# BlinkBoard.net
KiCad netlist of a schematic drawn in Altium Designer
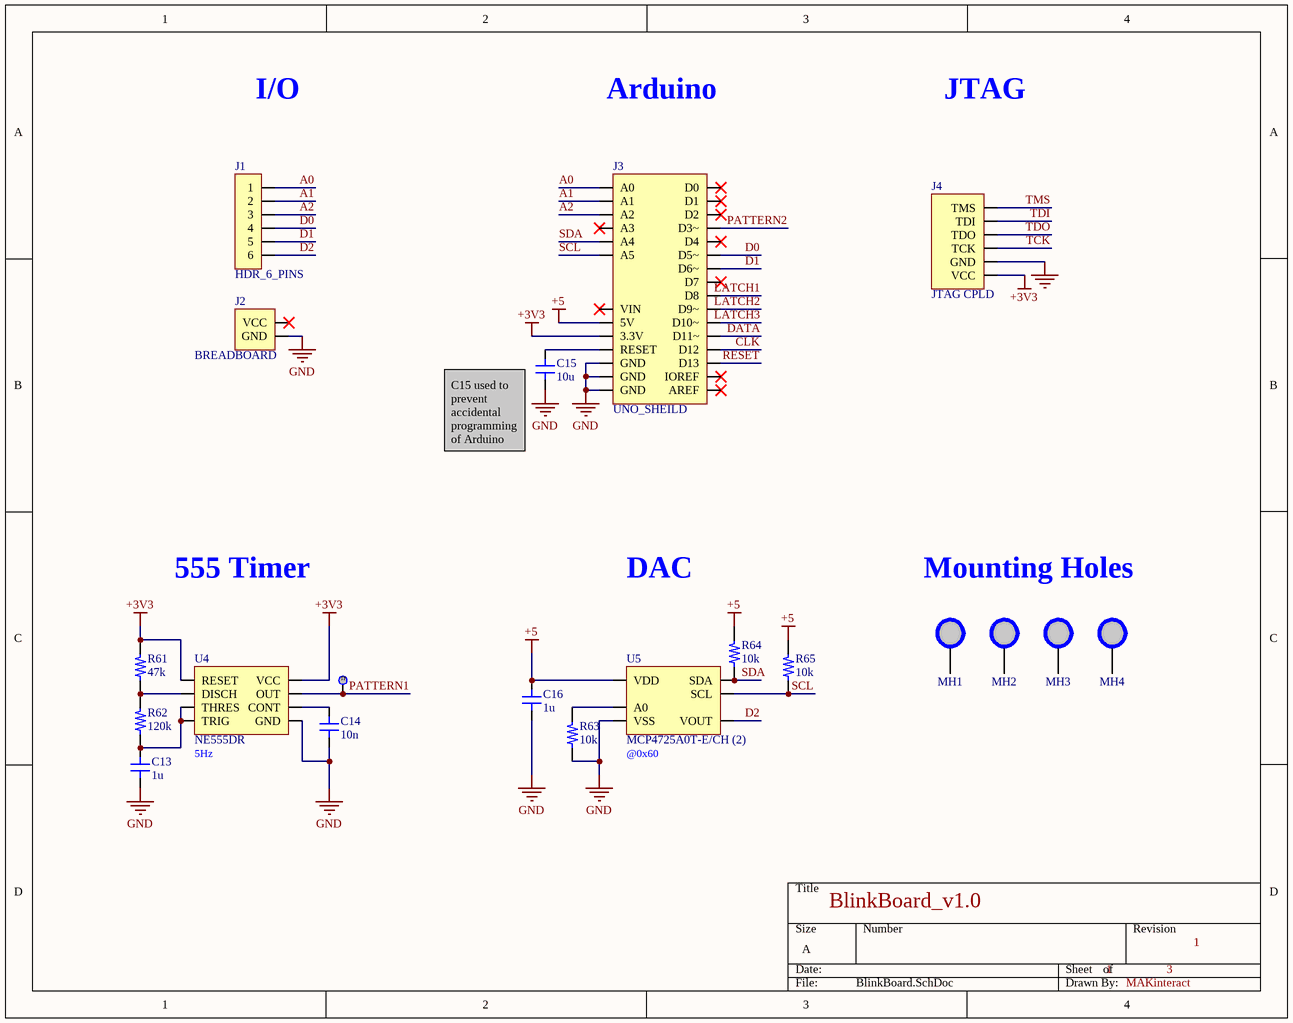
[diagram p0: BlinkBoard.SchDoc]

(export (version "E")
  (design (tool "Eeschema 10.0.6"))
  (components
    (comp (ref "C13")
      (value "1u")
      (footprint "C0805")
      (fields
        (field (name "MANUFACTURER") "Yageo")
        (field (name "MANUFACTURER PART NUMBER") "CC0805ZRY5V8BB105")
        (field (name "TOLERANCE") "80%")
      )
      (libsource (lib "LightBoard_v1.0") (part "C0805_1u"))
    )
    (comp (ref "C14")
      (value "10n")
      (footprint "C0402")
      (description "Cap Ceramic 0.01uF 10V X7R 10% SMD 0402 125C Paper T/R")
      (fields
        (field (name "MANUFACTURER") "Yageo")
        (field (name "MANUFACTURER PART NUMBER") "CC0402KRX7R6BB103")
      )
      (libsource (lib "LightBoard_v1.0") (part "C0402_10n"))
    )
    (comp (ref "C15")
      (value "10u")
      (footprint "C0805")
      (description "Cap Ceramic 10uF 6.3V X5R 10% SMD 0805 85C Paper T/R")
      (fields
        (field (name "MANUFACTURER") "Yageo")
        (field (name "MANUFACTURER PART NUMBER") "CC0805KRX5R5BB106")
      )
      (libsource (lib "BlinkBoard") (part "C0804_10u"))
    )
    (comp (ref "C16")
      (value "1u")
      (footprint "C0805")
      (fields
        (field (name "MANUFACTURER") "Yageo")
        (field (name "MANUFACTURER PART NUMBER") "CC0805ZRY5V8BB105")
        (field (name "TOLERANCE") "80%")
      )
      (libsource (lib "LightBoard_v1.0") (part "C0805_1u"))
    )
    (comp (ref "J1")
      (value "HDR_6_PINS")
      (footprint "HDR6_100mil")
      (description "Sockets to connect to Arduino pins")
      (libsource (lib "LightBoard_v1.0") (part "H_ARDUPINS"))
    )
    (comp (ref "J2")
      (value "BREADBOARD")
      (footprint "BREADBOARD")
      (description "26*2 ROWS")
      (libsource (lib "LightBoard_v1.0") (part "BREADBOARD"))
    )
    (comp (ref "J3")
      (value "UNO_SHEILD")
      (footprint "ARDUINO_UNO_SHIELD")
      (description "Arduino UNO shield")
      (fields (field (name "MANUFACTURER") "Arduino") (field (name "MANUFACTURER PART NUMBER") "A000073"))
      (libsource (lib "LightBoard_v1.0") (part "ARDUINO_UNO_SHIELD"))
    )
    (comp (ref "J4")
      (value "JTAG CPLD")
      (footprint "JTAG")
      (description "Socket to connect to JTAG")
      (libsource (lib "LightBoard_v1.0") (part "H_JTAG"))
    )
    (comp (ref "MH1")
      (value "MH 3.2mm NP")
      (footprint "MH3.2MM")
      (description "Mounting hole 3.2mm non plated")
      (libsource (lib "LightBoard_v1.0") (part "MHNP"))
    )
    (comp (ref "MH2")
      (value "MH 3.2mm NP")
      (footprint "MH3.2MM")
      (description "Mounting hole 3.2mm non plated")
      (libsource (lib "LightBoard_v1.0") (part "MHNP"))
    )
    (comp (ref "MH3")
      (value "MH 3.2mm NP")
      (footprint "MH3.2MM")
      (description "Mounting hole 3.2mm non plated")
      (libsource (lib "LightBoard_v1.0") (part "MHNP"))
    )
    (comp (ref "MH4")
      (value "MH 3.2mm NP")
      (footprint "MH3.2MM")
      (description "Mounting hole 3.2mm non plated")
      (libsource (lib "LightBoard_v1.0") (part "MHNP"))
    )
    (comp (ref "R61")
      (value "47k")
      (footprint "RES0402")
      (fields
        (field (name "MANUFACTURER") "Yageo")
        (field (name "MANUFACTURER PART NUMBER") "RC0402JR-0747KL")
        (field (name "TOLERANCE") "5%")
      )
      (libsource (lib "LightBoard_v1.0") (part "R0402_47K"))
    )
    (comp (ref "R62")
      (value "120k")
      (footprint "RES0402")
      (description "RES SMD 120K OHM 5% 1/16W 0402")
      (fields
        (field (name "MANUFACTURER") "Yageo")
        (field (name "MANUFACTURER PART NUMBER") "RC0402JR-07120KL")
      )
      (libsource (lib "LightBoard_v1.0") (part "R0402_120K"))
    )
    (comp (ref "R63")
      (value "10k")
      (footprint "RES0402")
      (description "RES SMD 10K OHM 1% 1/16W 0402")
      (fields
        (field (name "MANUFACTURER") "Yageo")
        (field (name "MANUFACTURER PART NUMBER") "RC0402FR-0710KP")
      )
      (libsource (lib "LightBoard_v1.0") (part "R0402_10K"))
    )
    (comp (ref "R64")
      (value "10k")
      (footprint "RES0402")
      (description "RES SMD 10K OHM 1% 1/16W 0402")
      (fields
        (field (name "MANUFACTURER") "Yageo")
        (field (name "MANUFACTURER PART NUMBER") "RC0402FR-0710KP")
      )
      (libsource (lib "LightBoard_v1.0") (part "R0402_10K"))
    )
    (comp (ref "R65")
      (value "10k")
      (footprint "RES0402")
      (description "RES SMD 10K OHM 1% 1/16W 0402")
      (fields
        (field (name "MANUFACTURER") "Yageo")
        (field (name "MANUFACTURER PART NUMBER") "RC0402FR-0710KP")
      )
      (libsource (lib "LightBoard_v1.0") (part "R0402_10K"))
    )
    (comp (ref "TP1")
      (value "TEST POINT")
      (footprint "TEST POINT")
      (libsource (lib "LightBoard_v1.0") (part "TEST POINT"))
    )
    (comp (ref "U4")
      (value "NE555DR")
      (footprint "8-SOIC")
      (description "TEXAS INSTRUMENTS         NE555DR.             TIMER, SINGLE, 500KHZ, 16V, SOIC-8")
      (fields (field (name "MANUFACTURER") "Texas Instruments"))
      (libsource (lib "LightBoard_v1.0") (part "555"))
    )
    (comp (ref "U5")
      (value "MCP4725A0T-E/CH (2)")
      (footprint "SOT23-6")
      (description "DAC 1-CH Resistor-String 12-bit 6-Pin SOT-23A T/R")
      (fields
        (field (name "MANUFACTURER") "Microchip")
        (field (name "MANUFACTURER PART NUMBER") "MCP4725A0T-E/CH")
      )
      (libsource (lib "LightBoard_v1.0") (part "MCP4725A0T"))
    )
  )
  (nets
    (net (code "1") (name "+3V3") (class "Default")
      (node (ref "J3") (pin "27") (pinfunction "3.3V_27") (pintype "passive"))
      (node (ref "J4") (pin "6") (pinfunction "VCC_6") (pintype "passive"))
      (node (ref "R61") (pin "2") (pinfunction "2_2") (pintype "passive"))
      (node (ref "U4") (pin "4") (pinfunction "RESET_4") (pintype "passive"))
      (node (ref "U4") (pin "8") (pinfunction "VCC_8") (pintype "passive"))
    )
    (net (code "2") (name "+5") (class "Default")
      (node (ref "C16") (pin "2") (pinfunction "2_2") (pintype "passive"))
      (node (ref "J3") (pin "26") (pinfunction "5V_26") (pintype "passive"))
      (node (ref "R64") (pin "2") (pinfunction "2_2") (pintype "passive"))
      (node (ref "R65") (pin "2") (pinfunction "2_2") (pintype "passive"))
      (node (ref "U5") (pin "3") (pinfunction "VDD_3") (pintype "passive"))
    )
    (net (code "3") (name "/A0") (class "Default")
      (node (ref "J1") (pin "1") (pinfunction "1_1") (pintype "passive"))
      (node (ref "J3") (pin "22") (pinfunction "A0_22") (pintype "passive"))
    )
    (net (code "4") (name "/A1") (class "Default")
      (node (ref "J1") (pin "2") (pinfunction "2_2") (pintype "passive"))
      (node (ref "J3") (pin "21") (pinfunction "A1_21") (pintype "passive"))
    )
    (net (code "5") (name "/A2") (class "Default")
      (node (ref "J1") (pin "3") (pinfunction "3_3") (pintype "passive"))
      (node (ref "J3") (pin "20") (pinfunction "A2_20") (pintype "passive"))
    )
    (net (code "6") (name "/CLK") (class "Default")
      (node (ref "J3") (pin "13") (pinfunction "D12_13") (pintype "passive"))
    )
    (net (code "7") (name "/D0") (class "Default")
      (node (ref "J1") (pin "4") (pinfunction "4_4") (pintype "passive"))
      (node (ref "J3") (pin "6") (pinfunction "D5~_6") (pintype "passive"))
    )
    (net (code "8") (name "/D1") (class "Default")
      (node (ref "J1") (pin "5") (pinfunction "5_5") (pintype "passive"))
      (node (ref "J3") (pin "7") (pinfunction "D6~_7") (pintype "passive"))
    )
    (net (code "9") (name "/D2") (class "Default")
      (node (ref "J1") (pin "6") (pinfunction "6_6") (pintype "passive"))
      (node (ref "U5") (pin "1") (pinfunction "VOUT_1") (pintype "passive"))
    )
    (net (code "10") (name "/DATA") (class "Default")
      (node (ref "J3") (pin "12") (pinfunction "D11~_12") (pintype "passive"))
    )
    (net (code "11") (name "/LATCH1") (class "Default")
      (node (ref "J3") (pin "9") (pinfunction "D8_9") (pintype "passive"))
    )
    (net (code "12") (name "/LATCH2") (class "Default")
      (node (ref "J3") (pin "10") (pinfunction "D9~_10") (pintype "passive"))
    )
    (net (code "13") (name "/LATCH3") (class "Default")
      (node (ref "J3") (pin "11") (pinfunction "D10~_11") (pintype "passive"))
    )
    (net (code "14") (name "/PATTERN1") (class "Default")
      (node (ref "TP1") (pin "1") (pinfunction "1_1") (pintype "passive"))
      (node (ref "U4") (pin "3") (pinfunction "OUT_3") (pintype "passive"))
    )
    (net (code "15") (name "/PATTERN2") (class "Default")
      (node (ref "J3") (pin "4") (pinfunction "D3~_4") (pintype "passive"))
    )
    (net (code "16") (name "/RESET") (class "Default")
      (node (ref "J3") (pin "14") (pinfunction "D13_14") (pintype "passive"))
    )
    (net (code "17") (name "/SCL") (class "Default")
      (node (ref "J3") (pin "17") (pinfunction "A5_17") (pintype "passive"))
      (node (ref "R65") (pin "1") (pinfunction "1_1") (pintype "passive"))
      (node (ref "U5") (pin "5") (pinfunction "SCL_5") (pintype "passive"))
    )
    (net (code "18") (name "/SDA") (class "Default")
      (node (ref "J3") (pin "18") (pinfunction "A4_18") (pintype "passive"))
      (node (ref "R64") (pin "1") (pinfunction "1_1") (pintype "passive"))
      (node (ref "U5") (pin "4") (pinfunction "SDA_4") (pintype "passive"))
    )
    (net (code "19") (name "/TCK") (class "Default")
      (node (ref "J4") (pin "4") (pinfunction "TCK_4") (pintype "passive"))
    )
    (net (code "20") (name "/TDI") (class "Default")
      (node (ref "J4") (pin "2") (pinfunction "TDI_2") (pintype "passive"))
    )
    (net (code "21") (name "/TDO") (class "Default")
      (node (ref "J4") (pin "3") (pinfunction "TDO_3") (pintype "passive"))
    )
    (net (code "22") (name "/TMS") (class "Default")
      (node (ref "J4") (pin "1") (pinfunction "TMS_1") (pintype "passive"))
    )
    (net (code "23") (name "GND") (class "Default")
      (node (ref "C13") (pin "1") (pinfunction "1_1") (pintype "passive"))
      (node (ref "C14") (pin "1") (pinfunction "1_1") (pintype "passive"))
      (node (ref "C15") (pin "1") (pinfunction "1_1") (pintype "passive"))
      (node (ref "C16") (pin "1") (pinfunction "1_1") (pintype "passive"))
      (node (ref "J2") (pin "2") (pinfunction "GND_2") (pintype "passive"))
      (node (ref "J3") (pin "15") (pinfunction "GND_15") (pintype "passive"))
      (node (ref "J3") (pin "24") (pinfunction "GND_24") (pintype "passive"))
      (node (ref "J3") (pin "25") (pinfunction "GND_25") (pintype "passive"))
      (node (ref "J4") (pin "5") (pinfunction "GND_5") (pintype "passive"))
      (node (ref "R63") (pin "1") (pinfunction "1_1") (pintype "passive"))
      (node (ref "U4") (pin "1") (pinfunction "GND_1") (pintype "passive"))
      (node (ref "U5") (pin "2") (pinfunction "VSS_2") (pintype "passive"))
    )
    (net (code "24") (name "Net-(J3-RESET)") (class "Default")
      (node (ref "C15") (pin "2") (pinfunction "2_2") (pintype "passive"))
      (node (ref "J3") (pin "28") (pinfunction "RESET_28") (pintype "passive"))
    )
    (net (code "25") (name "Net-(U4-CONT)") (class "Default")
      (node (ref "C14") (pin "2") (pinfunction "2_2") (pintype "passive"))
      (node (ref "U4") (pin "5") (pinfunction "CONT_5") (pintype "passive"))
    )
    (net (code "26") (name "Net-(U4-DISCH)") (class "Default")
      (node (ref "R61") (pin "1") (pinfunction "1_1") (pintype "passive"))
      (node (ref "R62") (pin "2") (pinfunction "2_2") (pintype "passive"))
      (node (ref "U4") (pin "7") (pinfunction "DISCH_7") (pintype "passive"))
    )
    (net (code "27") (name "Net-(U4-THRES)") (class "Default")
      (node (ref "C13") (pin "2") (pinfunction "2_2") (pintype "passive"))
      (node (ref "R62") (pin "1") (pinfunction "1_1") (pintype "passive"))
      (node (ref "U4") (pin "2") (pinfunction "TRIG_2") (pintype "passive"))
      (node (ref "U4") (pin "6") (pinfunction "THRES_6") (pintype "passive"))
    )
    (net (code "28") (name "Net-(U5-A0)") (class "Default")
      (node (ref "R63") (pin "2") (pinfunction "2_2") (pintype "passive"))
      (node (ref "U5") (pin "6") (pinfunction "A0_6") (pintype "passive"))
    )
    (net (code "29") (name "unconnected-(J2-VCC-Pad1)") (class "Default")
      (node (ref "J2") (pin "1") (pinfunction "VCC_1") (pintype "passive+no_connect"))
    )
    (net (code "30") (name "unconnected-(J3-A3-Pad19)") (class "Default")
      (node (ref "J3") (pin "19") (pinfunction "A3_19") (pintype "passive+no_connect"))
    )
    (net (code "31") (name "unconnected-(J3-AREF-Pad16)") (class "Default")
      (node (ref "J3") (pin "16") (pinfunction "AREF_16") (pintype "passive+no_connect"))
    )
    (net (code "32") (name "unconnected-(J3-D0-Pad1)") (class "Default")
      (node (ref "J3") (pin "1") (pinfunction "D0_1") (pintype "passive+no_connect"))
    )
    (net (code "33") (name "unconnected-(J3-D1-Pad2)") (class "Default")
      (node (ref "J3") (pin "2") (pinfunction "D1_2") (pintype "passive+no_connect"))
    )
    (net (code "34") (name "unconnected-(J3-D2-Pad3)") (class "Default")
      (node (ref "J3") (pin "3") (pinfunction "D2_3") (pintype "passive+no_connect"))
    )
    (net (code "35") (name "unconnected-(J3-D4-Pad5)") (class "Default")
      (node (ref "J3") (pin "5") (pinfunction "D4_5") (pintype "passive+no_connect"))
    )
    (net (code "36") (name "unconnected-(J3-D7-Pad8)") (class "Default")
      (node (ref "J3") (pin "8") (pinfunction "D7_8") (pintype "passive+no_connect"))
    )
    (net (code "37") (name "unconnected-(J3-IOREF-Pad29)") (class "Default")
      (node (ref "J3") (pin "29") (pinfunction "IOREF_29") (pintype "passive+no_connect"))
    )
    (net (code "38") (name "unconnected-(J3-VIN-Pad23)") (class "Default")
      (node (ref "J3") (pin "23") (pinfunction "VIN_23") (pintype "passive+no_connect"))
    )
    (net (code "39") (name "unconnected-(MH1-Pad1)") (class "Default")
      (node (ref "MH1") (pin "1") (pinfunction "1_1") (pintype "passive"))
    )
    (net (code "40") (name "unconnected-(MH2-Pad1)") (class "Default")
      (node (ref "MH2") (pin "1") (pinfunction "1_1") (pintype "passive"))
    )
    (net (code "41") (name "unconnected-(MH3-Pad1)") (class "Default")
      (node (ref "MH3") (pin "1") (pinfunction "1_1") (pintype "passive"))
    )
    (net (code "42") (name "unconnected-(MH4-Pad1)") (class "Default")
      (node (ref "MH4") (pin "1") (pinfunction "1_1") (pintype "passive"))
    )
  )
)
